# SAMD21E_Uno_unit.net
KiCad netlist of a schematic drawn in EAGLE
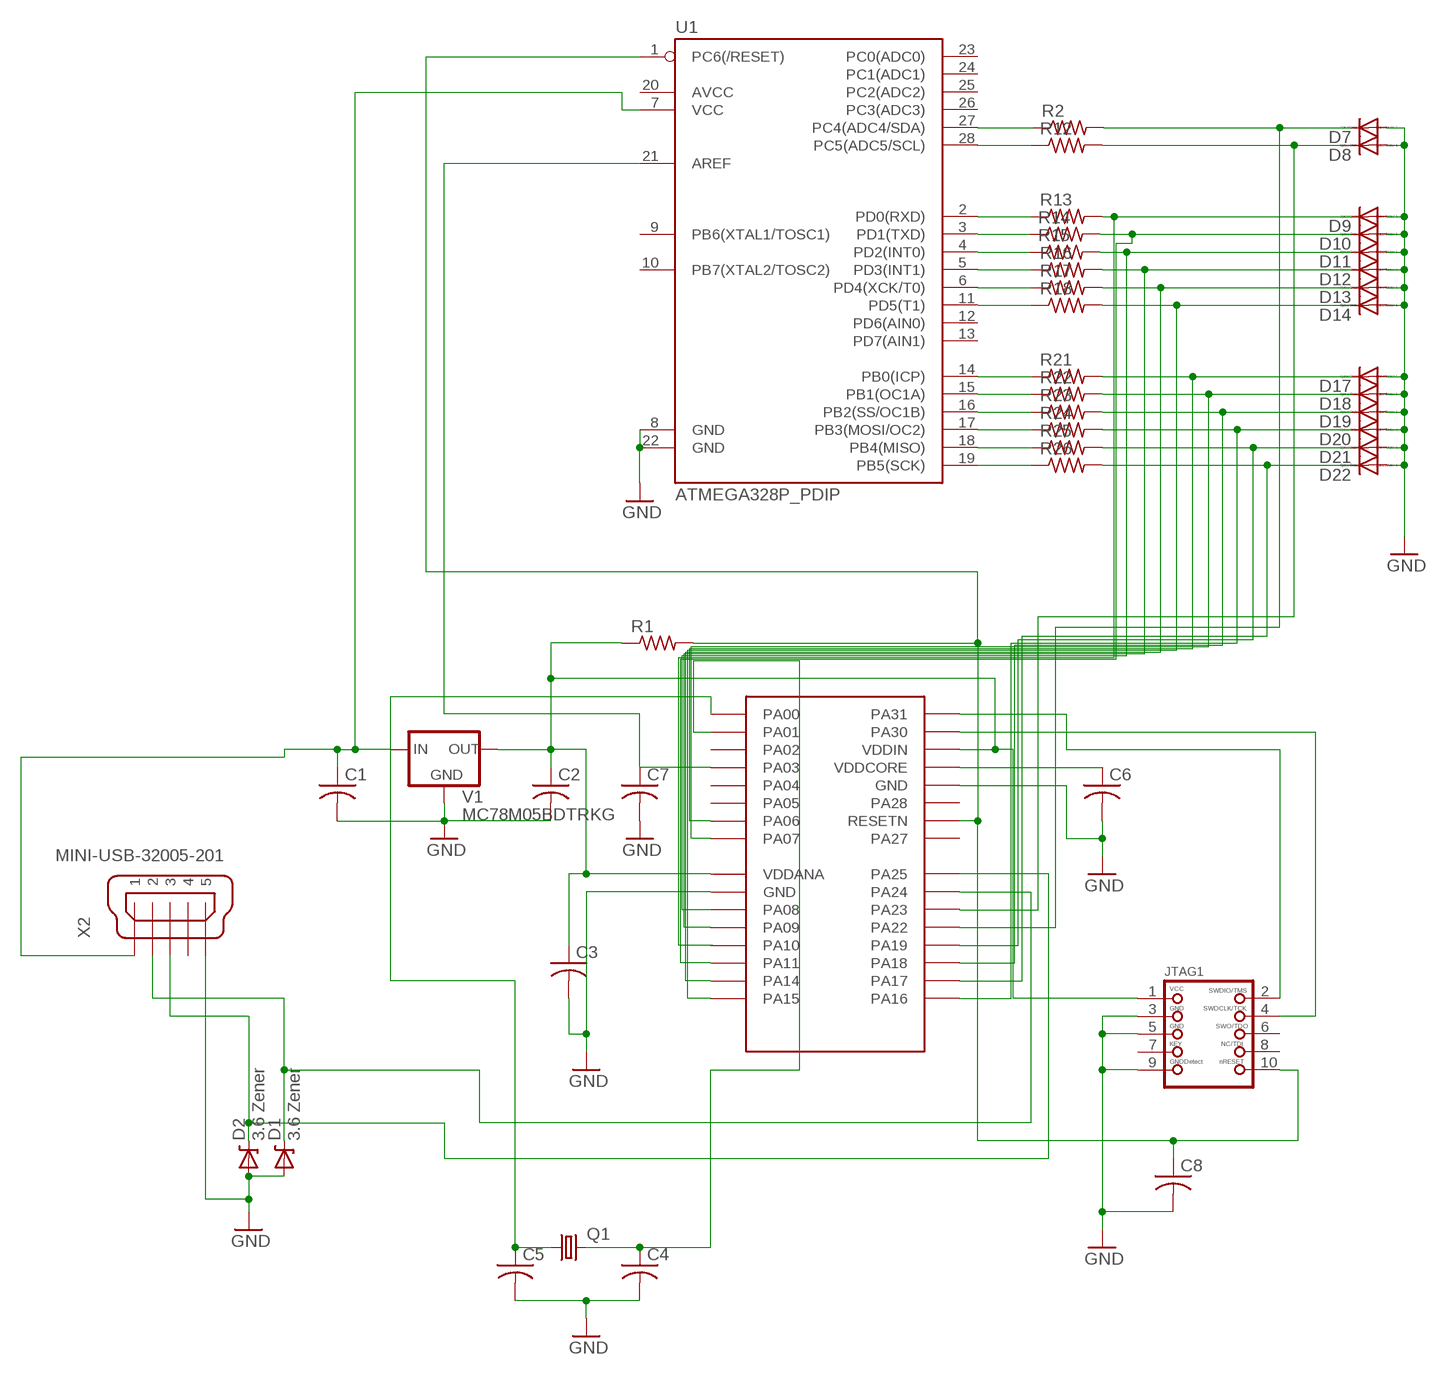
[diagram p0: schematic, sheet 1]

(export (version "E")
  (design (tool "Eeschema 10.0.6"))
  (components
    (comp (ref "C1")
      (value "C-USC0603K")
      (footprint "eagle-import:C0603K")
      (libsource (lib "eagle-import") (part "C-USC0603K"))
    )
    (comp (ref "C2")
      (value "C-USC0603K")
      (footprint "eagle-import:C0603K")
      (libsource (lib "eagle-import") (part "C-USC0603K"))
    )
    (comp (ref "C3")
      (value "C-USC0603")
      (footprint "eagle-import:C0603")
      (libsource (lib "eagle-import") (part "resistor_C-USC0603"))
    )
    (comp (ref "C4")
      (value "C-USC0603K")
      (footprint "eagle-import:C0603K")
      (libsource (lib "eagle-import") (part "resistor_C-USC0603K"))
    )
    (comp (ref "C5")
      (value "C-USC0603K")
      (footprint "eagle-import:C0603K")
      (libsource (lib "eagle-import") (part "resistor_C-USC0603K"))
    )
    (comp (ref "C6")
      (value "C-USC0603K")
      (footprint "eagle-import:C0603K")
      (libsource (lib "eagle-import") (part "C-USC0603K"))
    )
    (comp (ref "C7")
      (value "C-USC0603K")
      (footprint "eagle-import:C0603K")
      (libsource (lib "eagle-import") (part "C-USC0603K"))
    )
    (comp (ref "C8")
      (value "C-USC0603K")
      (footprint "eagle-import:C0603K")
      (libsource (lib "eagle-import") (part "C-USC0603K"))
    )
    (comp (ref "D1")
      (value "3.6 Zener")
      (footprint "eagle-import:SOD-323")
      (libsource (lib "eagle-import") (part "DIODE-ZENER-BZT52"))
    )
    (comp (ref "D2")
      (value "3.6 Zener")
      (footprint "eagle-import:SOD-323")
      (libsource (lib "eagle-import") (part "DIODE-ZENER-BZT52"))
    )
    (comp (ref "D7")
      (value "DIODE-SOD323-W")
      (footprint "eagle-import:SOD323-W")
      (libsource (lib "eagle-import") (part "DIODE-SOD323-W"))
    )
    (comp (ref "D8")
      (value "DIODE-SOD323-W")
      (footprint "eagle-import:SOD323-W")
      (libsource (lib "eagle-import") (part "DIODE-SOD323-W"))
    )
    (comp (ref "D9")
      (value "DIODE-SOD323-W")
      (footprint "eagle-import:SOD323-W")
      (libsource (lib "eagle-import") (part "DIODE-SOD323-W"))
    )
    (comp (ref "D10")
      (value "DIODE-SOD323-W")
      (footprint "eagle-import:SOD323-W")
      (libsource (lib "eagle-import") (part "DIODE-SOD323-W"))
    )
    (comp (ref "D11")
      (value "DIODE-SOD323-W")
      (footprint "eagle-import:SOD323-W")
      (libsource (lib "eagle-import") (part "DIODE-SOD323-W"))
    )
    (comp (ref "D12")
      (value "DIODE-SOD323-W")
      (footprint "eagle-import:SOD323-W")
      (libsource (lib "eagle-import") (part "DIODE-SOD323-W"))
    )
    (comp (ref "D13")
      (value "DIODE-SOD323-W")
      (footprint "eagle-import:SOD323-W")
      (libsource (lib "eagle-import") (part "DIODE-SOD323-W"))
    )
    (comp (ref "D14")
      (value "DIODE-SOD323-W")
      (footprint "eagle-import:SOD323-W")
      (libsource (lib "eagle-import") (part "DIODE-SOD323-W"))
    )
    (comp (ref "D17")
      (value "DIODE-SOD323-W")
      (footprint "eagle-import:SOD323-W")
      (libsource (lib "eagle-import") (part "DIODE-SOD323-W"))
    )
    (comp (ref "D18")
      (value "DIODE-SOD323-W")
      (footprint "eagle-import:SOD323-W")
      (libsource (lib "eagle-import") (part "DIODE-SOD323-W"))
    )
    (comp (ref "D19")
      (value "DIODE-SOD323-W")
      (footprint "eagle-import:SOD323-W")
      (libsource (lib "eagle-import") (part "DIODE-SOD323-W"))
    )
    (comp (ref "D20")
      (value "DIODE-SOD323-W")
      (footprint "eagle-import:SOD323-W")
      (libsource (lib "eagle-import") (part "DIODE-SOD323-W"))
    )
    (comp (ref "D21")
      (value "DIODE-SOD323-W")
      (footprint "eagle-import:SOD323-W")
      (libsource (lib "eagle-import") (part "DIODE-SOD323-W"))
    )
    (comp (ref "D22")
      (value "DIODE-SOD323-W")
      (footprint "eagle-import:SOD323-W")
      (libsource (lib "eagle-import") (part "DIODE-SOD323-W"))
    )
    (comp (ref "JTAG1")
      (value "JTAG-CORTEXM3")
      (footprint "eagle-import:2X05_1.27MM_SMT")
      (libsource (lib "eagle-import") (part "JTAG-CORTEXM3"))
    )
    (comp (ref "Q1")
      (value "CRYSTALHC49UP")
      (footprint "eagle-import:HC49UP")
      (libsource (lib "eagle-import") (part "CRYSTALHC49UP"))
    )
    (comp (ref "R1")
      (value "R-US_R0603")
      (footprint "eagle-import:R0603")
      (libsource (lib "eagle-import") (part "R-US_R0603"))
    )
    (comp (ref "R2")
      (value "R-US_R0603")
      (footprint "eagle-import:R0603")
      (libsource (lib "eagle-import") (part "resistor_R-US_R0603"))
    )
    (comp (ref "R12")
      (value "R-US_R0603")
      (footprint "eagle-import:R0603")
      (libsource (lib "eagle-import") (part "resistor_R-US_R0603"))
    )
    (comp (ref "R13")
      (value "R-US_R0603")
      (footprint "eagle-import:R0603")
      (libsource (lib "eagle-import") (part "resistor_R-US_R0603"))
    )
    (comp (ref "R14")
      (value "R-US_R0603")
      (footprint "eagle-import:R0603")
      (libsource (lib "eagle-import") (part "resistor_R-US_R0603"))
    )
    (comp (ref "R15")
      (value "R-US_R0603")
      (footprint "eagle-import:R0603")
      (libsource (lib "eagle-import") (part "resistor_R-US_R0603"))
    )
    (comp (ref "R16")
      (value "R-US_R0603")
      (footprint "eagle-import:R0603")
      (libsource (lib "eagle-import") (part "resistor_R-US_R0603"))
    )
    (comp (ref "R17")
      (value "R-US_R0603")
      (footprint "eagle-import:R0603")
      (libsource (lib "eagle-import") (part "resistor_R-US_R0603"))
    )
    (comp (ref "R18")
      (value "R-US_R0603")
      (footprint "eagle-import:R0603")
      (libsource (lib "eagle-import") (part "resistor_R-US_R0603"))
    )
    (comp (ref "R21")
      (value "R-US_R0603")
      (footprint "eagle-import:R0603")
      (libsource (lib "eagle-import") (part "resistor_R-US_R0603"))
    )
    (comp (ref "R22")
      (value "R-US_R0603")
      (footprint "eagle-import:R0603")
      (libsource (lib "eagle-import") (part "resistor_R-US_R0603"))
    )
    (comp (ref "R23")
      (value "R-US_R0603")
      (footprint "eagle-import:R0603")
      (libsource (lib "eagle-import") (part "resistor_R-US_R0603"))
    )
    (comp (ref "R24")
      (value "R-US_R0603")
      (footprint "eagle-import:R0603")
      (libsource (lib "eagle-import") (part "resistor_R-US_R0603"))
    )
    (comp (ref "R25")
      (value "R-US_R0603")
      (footprint "eagle-import:R0603")
      (libsource (lib "eagle-import") (part "resistor_R-US_R0603"))
    )
    (comp (ref "R26")
      (value "R-US_R0603")
      (footprint "eagle-import:R0603")
      (libsource (lib "eagle-import") (part "resistor_R-US_R0603"))
    )
    (comp (ref "U$8")
      (value "ATSAMD21E18A-AU")
      (footprint "eagle-import:32-TQFP")
      (libsource (lib "eagle-import") (part "ATSAMD21E18A-AU"))
    )
    (comp (ref "U1")
      (value "ATMEGA328P_PDIP")
      (footprint "eagle-import:DIL28-3")
      (libsource (lib "eagle-import") (part "ATMEGA328P_PDIP"))
    )
    (comp (ref "V1")
      (value "MC78M05BDTRKG")
      (footprint "eagle-import:DPACK")
      (libsource (lib "eagle-import") (part "LP2950?CDT-3.0"))
    )
    (comp (ref "X2")
      (value "MINI-USB-32005-201")
      (footprint "eagle-import:32005-201")
      (libsource (lib "eagle-import") (part "MINI-USB-32005-201"))
    )
  )
  (nets
    (net (code "1") (name "GND") (class "Default")
      (node (ref "C1") (pin "2") (pinfunction "2_2") (pintype "passive"))
      (node (ref "C2") (pin "2") (pinfunction "2_2") (pintype "passive"))
      (node (ref "C3") (pin "2") (pinfunction "2_2") (pintype "passive"))
      (node (ref "C4") (pin "2") (pinfunction "2_2") (pintype "passive"))
      (node (ref "C5") (pin "2") (pinfunction "2_2") (pintype "passive"))
      (node (ref "C6") (pin "2") (pinfunction "2_2") (pintype "passive"))
      (node (ref "C7") (pin "2") (pinfunction "2_2") (pintype "passive"))
      (node (ref "C8") (pin "2") (pinfunction "2_2") (pintype "passive"))
      (node (ref "D1") (pin "2") (pinfunction "A_2") (pintype "passive"))
      (node (ref "D10") (pin "A") (pinfunction "A_A") (pintype "passive"))
      (node (ref "D11") (pin "A") (pinfunction "A_A") (pintype "passive"))
      (node (ref "D12") (pin "A") (pinfunction "A_A") (pintype "passive"))
      (node (ref "D13") (pin "A") (pinfunction "A_A") (pintype "passive"))
      (node (ref "D14") (pin "A") (pinfunction "A_A") (pintype "passive"))
      (node (ref "D17") (pin "A") (pinfunction "A_A") (pintype "passive"))
      (node (ref "D18") (pin "A") (pinfunction "A_A") (pintype "passive"))
      (node (ref "D19") (pin "A") (pinfunction "A_A") (pintype "passive"))
      (node (ref "D2") (pin "2") (pinfunction "A_2") (pintype "passive"))
      (node (ref "D20") (pin "A") (pinfunction "A_A") (pintype "passive"))
      (node (ref "D21") (pin "A") (pinfunction "A_A") (pintype "passive"))
      (node (ref "D22") (pin "A") (pinfunction "A_A") (pintype "passive"))
      (node (ref "D7") (pin "A") (pinfunction "A_A") (pintype "passive"))
      (node (ref "D8") (pin "A") (pinfunction "A_A") (pintype "passive"))
      (node (ref "D9") (pin "A") (pinfunction "A_A") (pintype "passive"))
      (node (ref "JTAG1") (pin "3") (pinfunction "3_3") (pintype "passive"))
      (node (ref "JTAG1") (pin "5") (pinfunction "5_5") (pintype "passive"))
      (node (ref "JTAG1") (pin "9") (pinfunction "9_9") (pintype "passive"))
      (node (ref "U$8") (pin "10") (pinfunction "GND_10") (pintype "bidirectional"))
      (node (ref "U$8") (pin "28") (pinfunction "GND_28") (pintype "bidirectional"))
      (node (ref "U1") (pin "22") (pinfunction "GND_22") (pintype "bidirectional"))
      (node (ref "U1") (pin "8") (pinfunction "GND_8") (pintype "bidirectional"))
      (node (ref "V1") (pin "4") (pinfunction "GND_4") (pintype "input"))
      (node (ref "X2") (pin "5") (pinfunction "5_5") (pintype "passive"))
    )
    (net (code "2") (name "Net-(D1-C)") (class "Default")
      (node (ref "D1") (pin "1") (pinfunction "C_1") (pintype "passive"))
      (node (ref "U$8") (pin "23") (pinfunction "PA24_23") (pintype "bidirectional"))
      (node (ref "X2") (pin "2") (pinfunction "2_2") (pintype "passive"))
    )
    (net (code "3") (name "Net-(D2-C)") (class "Default")
      (node (ref "D2") (pin "1") (pinfunction "C_1") (pintype "passive"))
      (node (ref "U$8") (pin "24") (pinfunction "PA25_24") (pintype "bidirectional"))
      (node (ref "X2") (pin "3") (pinfunction "3_3") (pintype "passive"))
    )
    (net (code "4") (name "Net-(D9-PadC)") (class "Default")
      (node (ref "D9") (pin "C") (pinfunction "C_C") (pintype "passive"))
      (node (ref "R13") (pin "2") (pinfunction "2_2") (pintype "passive"))
    )
    (net (code "5") (name "Net-(U$8-PA00)") (class "Default")
      (node (ref "C5") (pin "1") (pinfunction "1_1") (pintype "passive"))
      (node (ref "Q1") (pin "1") (pinfunction "1_1") (pintype "passive"))
      (node (ref "U$8") (pin "1") (pinfunction "PA00_1") (pintype "bidirectional"))
    )
    (net (code "6") (name "Net-(U$8-PA01)") (class "Default")
      (node (ref "C4") (pin "1") (pinfunction "1_1") (pintype "passive"))
      (node (ref "Q1") (pin "2") (pinfunction "2_2") (pintype "passive"))
      (node (ref "U$8") (pin "2") (pinfunction "PA01_2") (pintype "bidirectional"))
    )
    (net (code "7") (name "Net-(U$8-PA03)") (class "Default")
      (node (ref "C7") (pin "1") (pinfunction "1_1") (pintype "passive"))
      (node (ref "U$8") (pin "4") (pinfunction "PA03_4") (pintype "bidirectional"))
      (node (ref "U1") (pin "21") (pinfunction "AREF_21") (pintype "bidirectional"))
    )
    (net (code "8") (name "Net-(U$8-PA06)") (class "Default")
      (node (ref "D17") (pin "C") (pinfunction "C_C") (pintype "passive"))
      (node (ref "R21") (pin "2") (pinfunction "2_2") (pintype "passive"))
      (node (ref "U$8") (pin "7") (pinfunction "PA06_7") (pintype "bidirectional"))
    )
    (net (code "9") (name "Net-(U$8-PA07)") (class "Default")
      (node (ref "D18") (pin "C") (pinfunction "C_C") (pintype "passive"))
      (node (ref "R22") (pin "2") (pinfunction "2_2") (pintype "passive"))
      (node (ref "U$8") (pin "8") (pinfunction "PA07_8") (pintype "bidirectional"))
    )
    (net (code "10") (name "Net-(U$8-PA08)") (class "Default")
      (node (ref "D11") (pin "C") (pinfunction "C_C") (pintype "passive"))
      (node (ref "R15") (pin "2") (pinfunction "2_2") (pintype "passive"))
      (node (ref "U$8") (pin "11") (pinfunction "PA08_11") (pintype "bidirectional"))
    )
    (net (code "11") (name "Net-(U$8-PA09)") (class "Default")
      (node (ref "D12") (pin "C") (pinfunction "C_C") (pintype "passive"))
      (node (ref "R16") (pin "2") (pinfunction "2_2") (pintype "passive"))
      (node (ref "U$8") (pin "12") (pinfunction "PA09_12") (pintype "bidirectional"))
    )
    (net (code "12") (name "Net-(U$8-PA11)") (class "Default")
      (node (ref "D10") (pin "C") (pinfunction "C_C") (pintype "passive"))
      (node (ref "R14") (pin "2") (pinfunction "2_2") (pintype "passive"))
      (node (ref "U$8") (pin "14") (pinfunction "PA11_14") (pintype "bidirectional"))
    )
    (net (code "13") (name "Net-(U$8-PA14)") (class "Default")
      (node (ref "D13") (pin "C") (pinfunction "C_C") (pintype "passive"))
      (node (ref "R17") (pin "2") (pinfunction "2_2") (pintype "passive"))
      (node (ref "U$8") (pin "15") (pinfunction "PA14_15") (pintype "bidirectional"))
    )
    (net (code "14") (name "Net-(U$8-PA15)") (class "Default")
      (node (ref "D14") (pin "C") (pinfunction "C_C") (pintype "passive"))
      (node (ref "R18") (pin "2") (pinfunction "2_2") (pintype "passive"))
      (node (ref "U$8") (pin "16") (pinfunction "PA15_16") (pintype "bidirectional"))
    )
    (net (code "15") (name "Net-(U$8-PA16)") (class "Default")
      (node (ref "D20") (pin "C") (pinfunction "C_C") (pintype "passive"))
      (node (ref "R24") (pin "2") (pinfunction "2_2") (pintype "passive"))
      (node (ref "U$8") (pin "17") (pinfunction "PA16_17") (pintype "bidirectional"))
    )
    (net (code "16") (name "Net-(U$8-PA17)") (class "Default")
      (node (ref "D22") (pin "C") (pinfunction "C_C") (pintype "passive"))
      (node (ref "R26") (pin "2") (pinfunction "2_2") (pintype "passive"))
      (node (ref "U$8") (pin "18") (pinfunction "PA17_18") (pintype "bidirectional"))
    )
    (net (code "17") (name "Net-(U$8-PA18)") (class "Default")
      (node (ref "D19") (pin "C") (pinfunction "C_C") (pintype "passive"))
      (node (ref "R23") (pin "2") (pinfunction "2_2") (pintype "passive"))
      (node (ref "U$8") (pin "19") (pinfunction "PA18_19") (pintype "bidirectional"))
    )
    (net (code "18") (name "Net-(U$8-PA19)") (class "Default")
      (node (ref "D21") (pin "C") (pinfunction "C_C") (pintype "passive"))
      (node (ref "R25") (pin "2") (pinfunction "2_2") (pintype "passive"))
      (node (ref "U$8") (pin "20") (pinfunction "PA19_20") (pintype "bidirectional"))
    )
    (net (code "19") (name "Net-(U$8-PA22)") (class "Default")
      (node (ref "D7") (pin "C") (pinfunction "C_C") (pintype "passive"))
      (node (ref "R2") (pin "2") (pinfunction "2_2") (pintype "passive"))
      (node (ref "U$8") (pin "21") (pinfunction "PA22_21") (pintype "bidirectional"))
    )
    (net (code "20") (name "Net-(U$8-PA23)") (class "Default")
      (node (ref "D8") (pin "C") (pinfunction "C_C") (pintype "passive"))
      (node (ref "R12") (pin "2") (pinfunction "2_2") (pintype "passive"))
      (node (ref "U$8") (pin "22") (pinfunction "PA23_22") (pintype "bidirectional"))
    )
    (net (code "21") (name "Net-(U$8-PA30)") (class "Default")
      (node (ref "JTAG1") (pin "4") (pinfunction "4_4") (pintype "passive"))
      (node (ref "U$8") (pin "31") (pinfunction "PA30_31") (pintype "bidirectional"))
    )
    (net (code "22") (name "Net-(U$8-PA31)") (class "Default")
      (node (ref "JTAG1") (pin "2") (pinfunction "2_2") (pintype "passive"))
      (node (ref "U$8") (pin "32") (pinfunction "PA31_32") (pintype "bidirectional"))
    )
    (net (code "23") (name "Net-(U$8-RESETN)") (class "Default")
      (node (ref "C8") (pin "1") (pinfunction "1_1") (pintype "passive"))
      (node (ref "JTAG1") (pin "10") (pinfunction "10_10") (pintype "passive"))
      (node (ref "R1") (pin "2") (pinfunction "2_2") (pintype "passive"))
      (node (ref "U$8") (pin "26") (pinfunction "RESETN_26") (pintype "bidirectional"))
      (node (ref "U1") (pin "1") (pinfunction "PC6(/RESET)_1") (pintype "bidirectional"))
    )
    (net (code "24") (name "Net-(U$8-VDDANA)") (class "Default")
      (node (ref "C2") (pin "1") (pinfunction "1_1") (pintype "passive"))
      (node (ref "C3") (pin "1") (pinfunction "1_1") (pintype "passive"))
      (node (ref "JTAG1") (pin "1") (pinfunction "1_1") (pintype "passive"))
      (node (ref "R1") (pin "1") (pinfunction "1_1") (pintype "passive"))
      (node (ref "U$8") (pin "30") (pinfunction "VDDIN_30") (pintype "bidirectional"))
      (node (ref "U$8") (pin "9") (pinfunction "VDDANA_9") (pintype "bidirectional"))
      (node (ref "V1") (pin "3") (pinfunction "OUT_3") (pintype "passive"))
    )
    (net (code "25") (name "Net-(U$8-VDDCORE)") (class "Default")
      (node (ref "C6") (pin "1") (pinfunction "1_1") (pintype "passive"))
      (node (ref "U$8") (pin "29") (pinfunction "VDDCORE_29") (pintype "bidirectional"))
    )
    (net (code "26") (name "Net-(U1-PB0(ICP))") (class "Default")
      (node (ref "R21") (pin "1") (pinfunction "1_1") (pintype "passive"))
      (node (ref "U1") (pin "14") (pinfunction "PB0(ICP)_14") (pintype "bidirectional"))
    )
    (net (code "27") (name "Net-(U1-PB1(OC1A))") (class "Default")
      (node (ref "R22") (pin "1") (pinfunction "1_1") (pintype "passive"))
      (node (ref "U1") (pin "15") (pinfunction "PB1(OC1A)_15") (pintype "bidirectional"))
    )
    (net (code "28") (name "Net-(U1-PB2(SS{slash}OC1B))") (class "Default")
      (node (ref "R23") (pin "1") (pinfunction "1_1") (pintype "passive"))
      (node (ref "U1") (pin "16") (pinfunction "PB2(SS/OC1B)_16") (pintype "bidirectional"))
    )
    (net (code "29") (name "Net-(U1-PB3(MOSI{slash}OC2))") (class "Default")
      (node (ref "R24") (pin "1") (pinfunction "1_1") (pintype "passive"))
      (node (ref "U1") (pin "17") (pinfunction "PB3(MOSI/OC2)_17") (pintype "bidirectional"))
    )
    (net (code "30") (name "Net-(U1-PB4(MISO))") (class "Default")
      (node (ref "R25") (pin "1") (pinfunction "1_1") (pintype "passive"))
      (node (ref "U1") (pin "18") (pinfunction "PB4(MISO)_18") (pintype "bidirectional"))
    )
    (net (code "31") (name "Net-(U1-PB5(SCK))") (class "Default")
      (node (ref "R26") (pin "1") (pinfunction "1_1") (pintype "passive"))
      (node (ref "U1") (pin "19") (pinfunction "PB5(SCK)_19") (pintype "bidirectional"))
    )
    (net (code "32") (name "Net-(U1-PC4(ADC4{slash}SDA))") (class "Default")
      (node (ref "R2") (pin "1") (pinfunction "1_1") (pintype "passive"))
      (node (ref "U1") (pin "27") (pinfunction "PC4(ADC4/SDA)_27") (pintype "bidirectional"))
    )
    (net (code "33") (name "Net-(U1-PC5(ADC5{slash}SCL))") (class "Default")
      (node (ref "R12") (pin "1") (pinfunction "1_1") (pintype "passive"))
      (node (ref "U1") (pin "28") (pinfunction "PC5(ADC5/SCL)_28") (pintype "bidirectional"))
    )
    (net (code "34") (name "Net-(U1-PD0(RXD))") (class "Default")
      (node (ref "R13") (pin "1") (pinfunction "1_1") (pintype "passive"))
      (node (ref "U1") (pin "2") (pinfunction "PD0(RXD)_2") (pintype "bidirectional"))
    )
    (net (code "35") (name "Net-(U1-PD1(TXD))") (class "Default")
      (node (ref "R14") (pin "1") (pinfunction "1_1") (pintype "passive"))
      (node (ref "U1") (pin "3") (pinfunction "PD1(TXD)_3") (pintype "bidirectional"))
    )
    (net (code "36") (name "Net-(U1-PD2(INT0))") (class "Default")
      (node (ref "R15") (pin "1") (pinfunction "1_1") (pintype "passive"))
      (node (ref "U1") (pin "4") (pinfunction "PD2(INT0)_4") (pintype "bidirectional"))
    )
    (net (code "37") (name "Net-(U1-PD3(INT1))") (class "Default")
      (node (ref "R16") (pin "1") (pinfunction "1_1") (pintype "passive"))
      (node (ref "U1") (pin "5") (pinfunction "PD3(INT1)_5") (pintype "bidirectional"))
    )
    (net (code "38") (name "Net-(U1-PD4(XCK{slash}T0))") (class "Default")
      (node (ref "R17") (pin "1") (pinfunction "1_1") (pintype "passive"))
      (node (ref "U1") (pin "6") (pinfunction "PD4(XCK/T0)_6") (pintype "bidirectional"))
    )
    (net (code "39") (name "Net-(U1-PD5(T1))") (class "Default")
      (node (ref "R18") (pin "1") (pinfunction "1_1") (pintype "passive"))
      (node (ref "U1") (pin "11") (pinfunction "PD5(T1)_11") (pintype "bidirectional"))
    )
    (net (code "40") (name "Net-(U1-VCC)") (class "Default")
      (node (ref "C1") (pin "1") (pinfunction "1_1") (pintype "passive"))
      (node (ref "U1") (pin "7") (pinfunction "VCC_7") (pintype "bidirectional"))
      (node (ref "V1") (pin "1") (pinfunction "IN_1") (pintype "input"))
      (node (ref "X2") (pin "1") (pinfunction "1_1") (pintype "passive"))
    )
    (net (code "41") (name "unconnected-(JTAG1-Pad6)") (class "Default")
      (node (ref "JTAG1") (pin "6") (pinfunction "6_6") (pintype "passive"))
    )
    (net (code "42") (name "unconnected-(JTAG1-Pad7)") (class "Default")
      (node (ref "JTAG1") (pin "7") (pinfunction "7_7") (pintype "passive"))
    )
    (net (code "43") (name "unconnected-(JTAG1-Pad8)") (class "Default")
      (node (ref "JTAG1") (pin "8") (pinfunction "8_8") (pintype "passive"))
    )
    (net (code "44") (name "unconnected-(U$8-PA02-Pad3)") (class "Default")
      (node (ref "U$8") (pin "3") (pinfunction "PA02_3") (pintype "bidirectional"))
    )
    (net (code "45") (name "unconnected-(U$8-PA04-Pad5)") (class "Default")
      (node (ref "U$8") (pin "5") (pinfunction "PA04_5") (pintype "bidirectional"))
    )
    (net (code "46") (name "unconnected-(U$8-PA05-Pad6)") (class "Default")
      (node (ref "U$8") (pin "6") (pinfunction "PA05_6") (pintype "bidirectional"))
    )
    (net (code "47") (name "unconnected-(U$8-PA10-Pad13)") (class "Default")
      (node (ref "U$8") (pin "13") (pinfunction "PA10_13") (pintype "bidirectional"))
    )
    (net (code "48") (name "unconnected-(U$8-PA27-Pad25)") (class "Default")
      (node (ref "U$8") (pin "25") (pinfunction "PA27_25") (pintype "bidirectional"))
    )
    (net (code "49") (name "unconnected-(U$8-PA28-Pad27)") (class "Default")
      (node (ref "U$8") (pin "27") (pinfunction "PA28_27") (pintype "bidirectional"))
    )
    (net (code "50") (name "unconnected-(U1-AVCC-Pad20)") (class "Default")
      (node (ref "U1") (pin "20") (pinfunction "AVCC_20") (pintype "bidirectional"))
    )
    (net (code "51") (name "unconnected-(U1-PB6(XTAL1{slash}TOSC1)-Pad9)") (class "Default")
      (node (ref "U1") (pin "9") (pinfunction "PB6(XTAL1/TOSC1)_9") (pintype "bidirectional"))
    )
    (net (code "52") (name "unconnected-(U1-PB7(XTAL2{slash}TOSC2)-Pad10)") (class "Default")
      (node (ref "U1") (pin "10") (pinfunction "PB7(XTAL2/TOSC2)_10") (pintype "bidirectional"))
    )
    (net (code "53") (name "unconnected-(U1-PC0(ADC0)-Pad23)") (class "Default")
      (node (ref "U1") (pin "23") (pinfunction "PC0(ADC0)_23") (pintype "bidirectional"))
    )
    (net (code "54") (name "unconnected-(U1-PC1(ADC1)-Pad24)") (class "Default")
      (node (ref "U1") (pin "24") (pinfunction "PC1(ADC1)_24") (pintype "bidirectional"))
    )
    (net (code "55") (name "unconnected-(U1-PC2(ADC2)-Pad25)") (class "Default")
      (node (ref "U1") (pin "25") (pinfunction "PC2(ADC2)_25") (pintype "bidirectional"))
    )
    (net (code "56") (name "unconnected-(U1-PC3(ADC3)-Pad26)") (class "Default")
      (node (ref "U1") (pin "26") (pinfunction "PC3(ADC3)_26") (pintype "bidirectional"))
    )
    (net (code "57") (name "unconnected-(U1-PD6(AIN0)-Pad12)") (class "Default")
      (node (ref "U1") (pin "12") (pinfunction "PD6(AIN0)_12") (pintype "bidirectional"))
    )
    (net (code "58") (name "unconnected-(U1-PD7(AIN1)-Pad13)") (class "Default")
      (node (ref "U1") (pin "13") (pinfunction "PD7(AIN1)_13") (pintype "bidirectional"))
    )
    (net (code "59") (name "unconnected-(X2-Pad4)") (class "Default")
      (node (ref "X2") (pin "4") (pinfunction "4_4") (pintype "passive"))
    )
  )
)
